# pmm.net
KiCad netlist of a schematic drawn in EAGLE
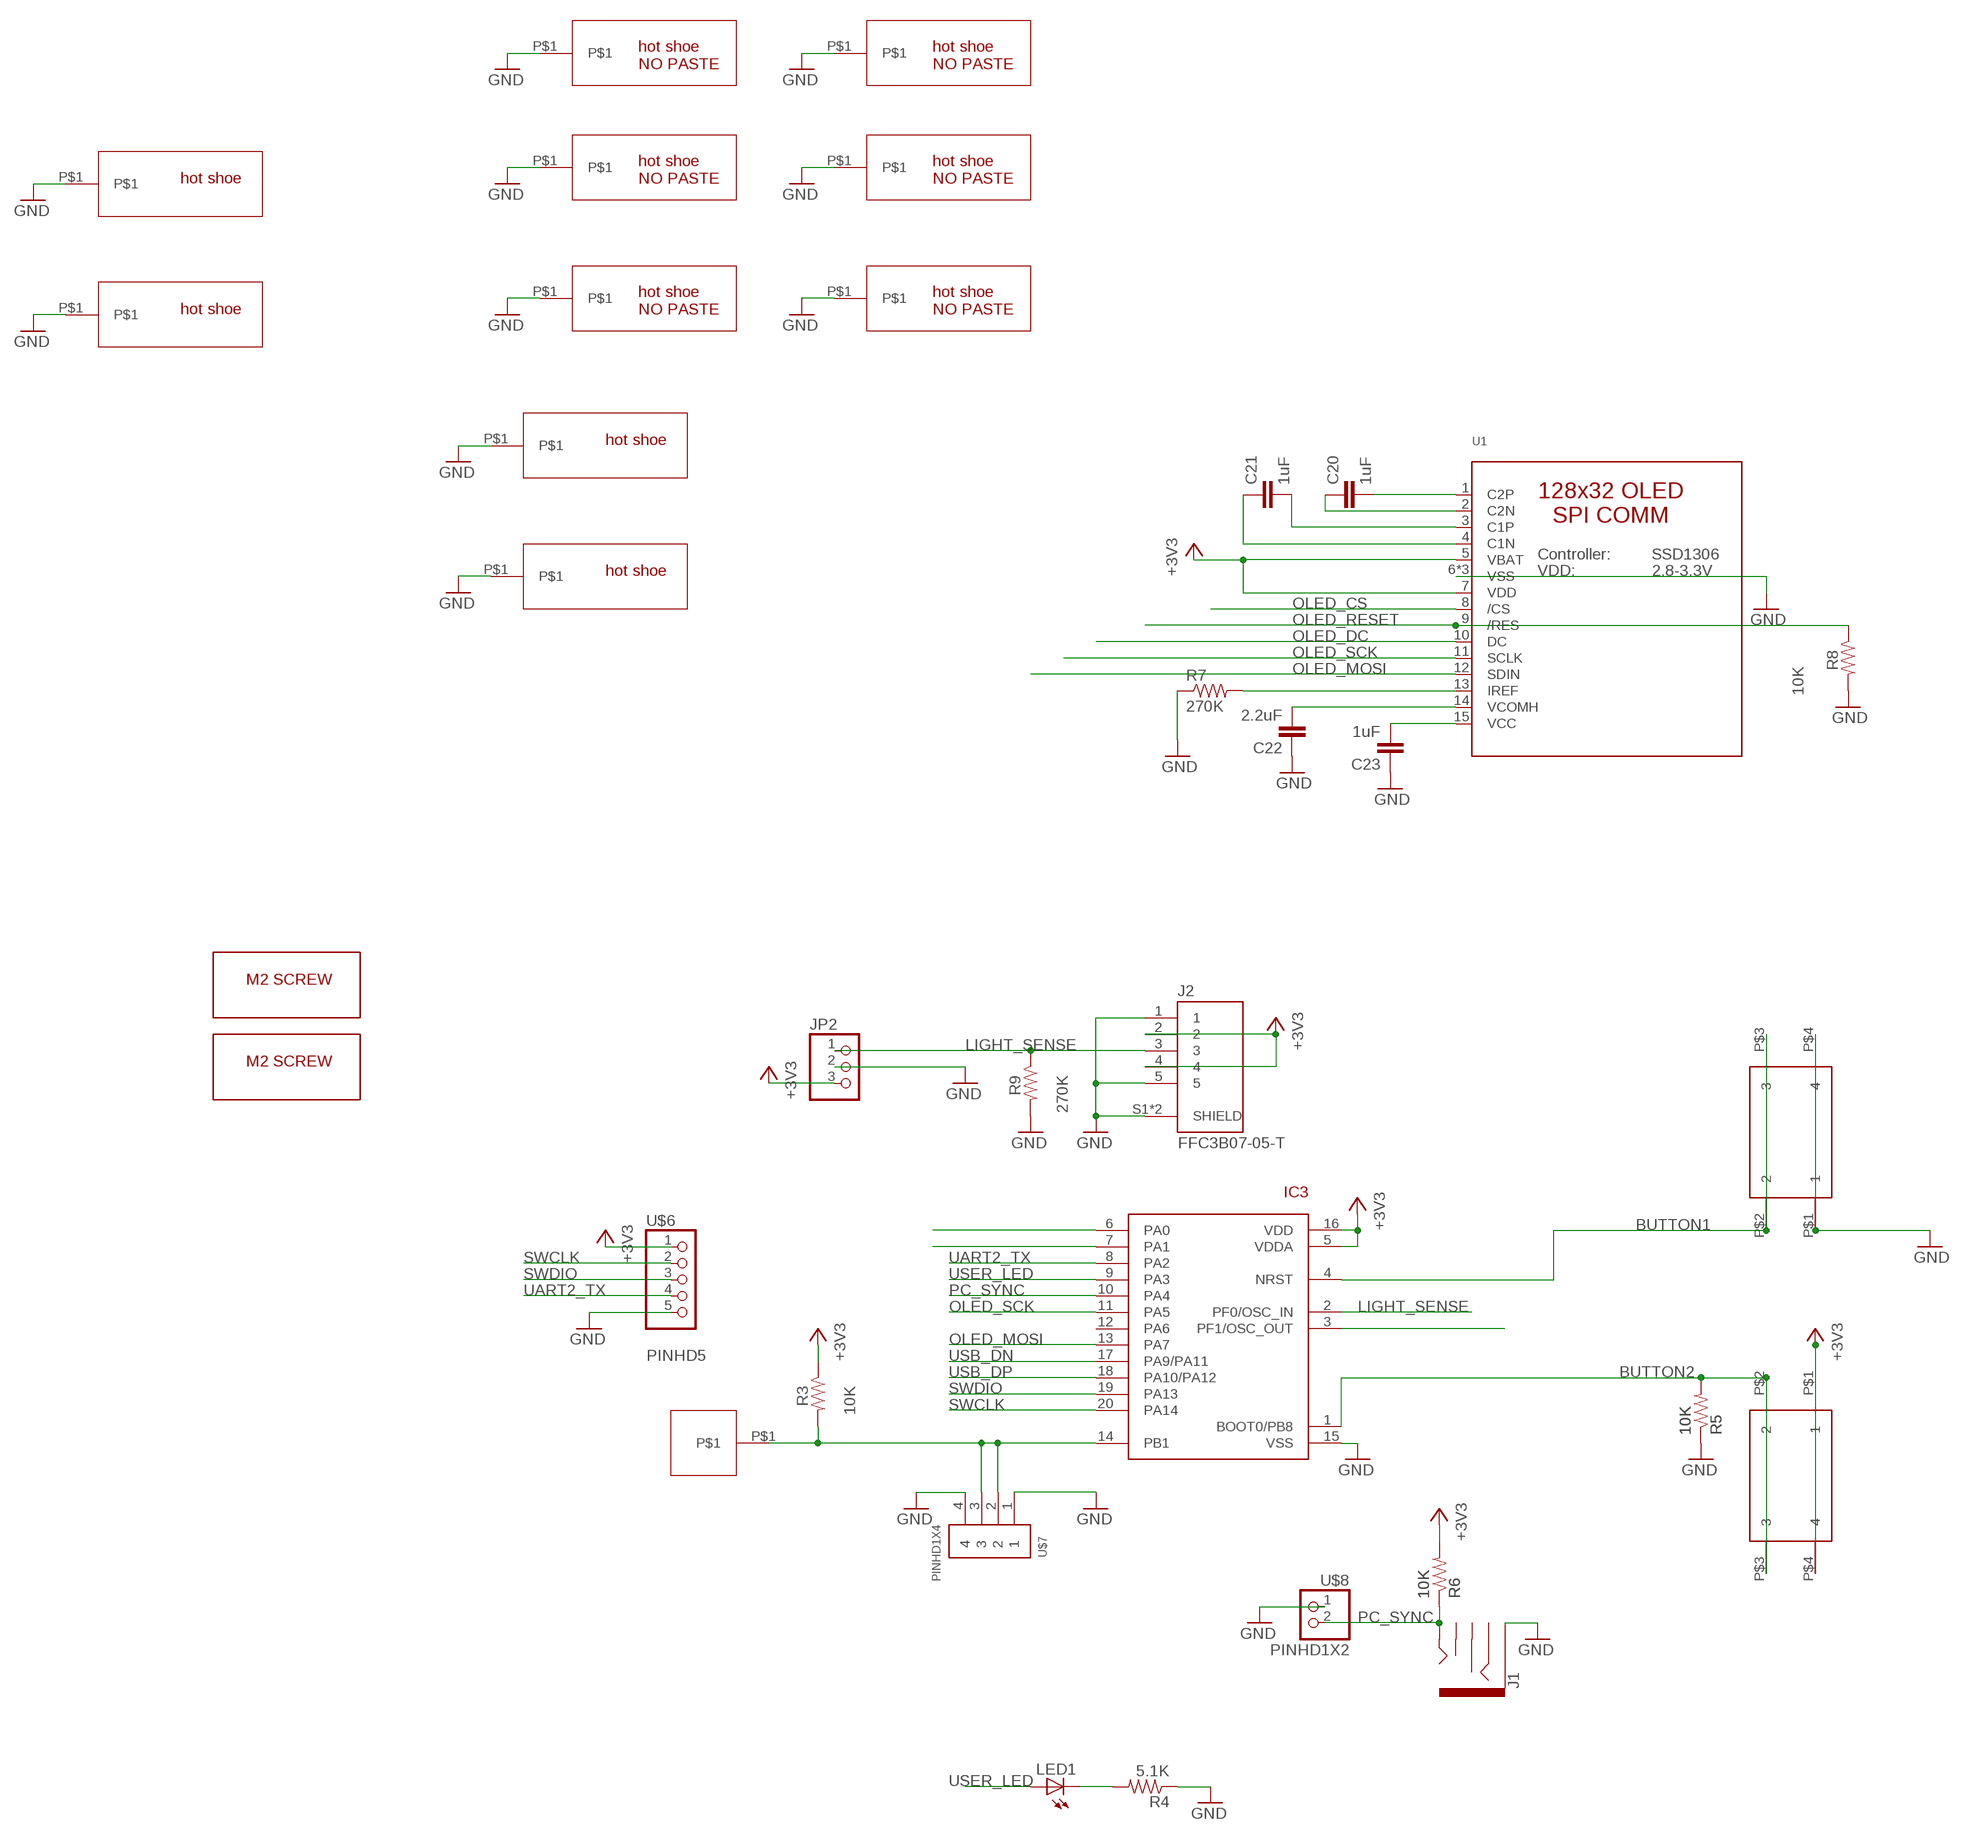
[diagram p0: schematic, sheet 1, part 1 of 2]
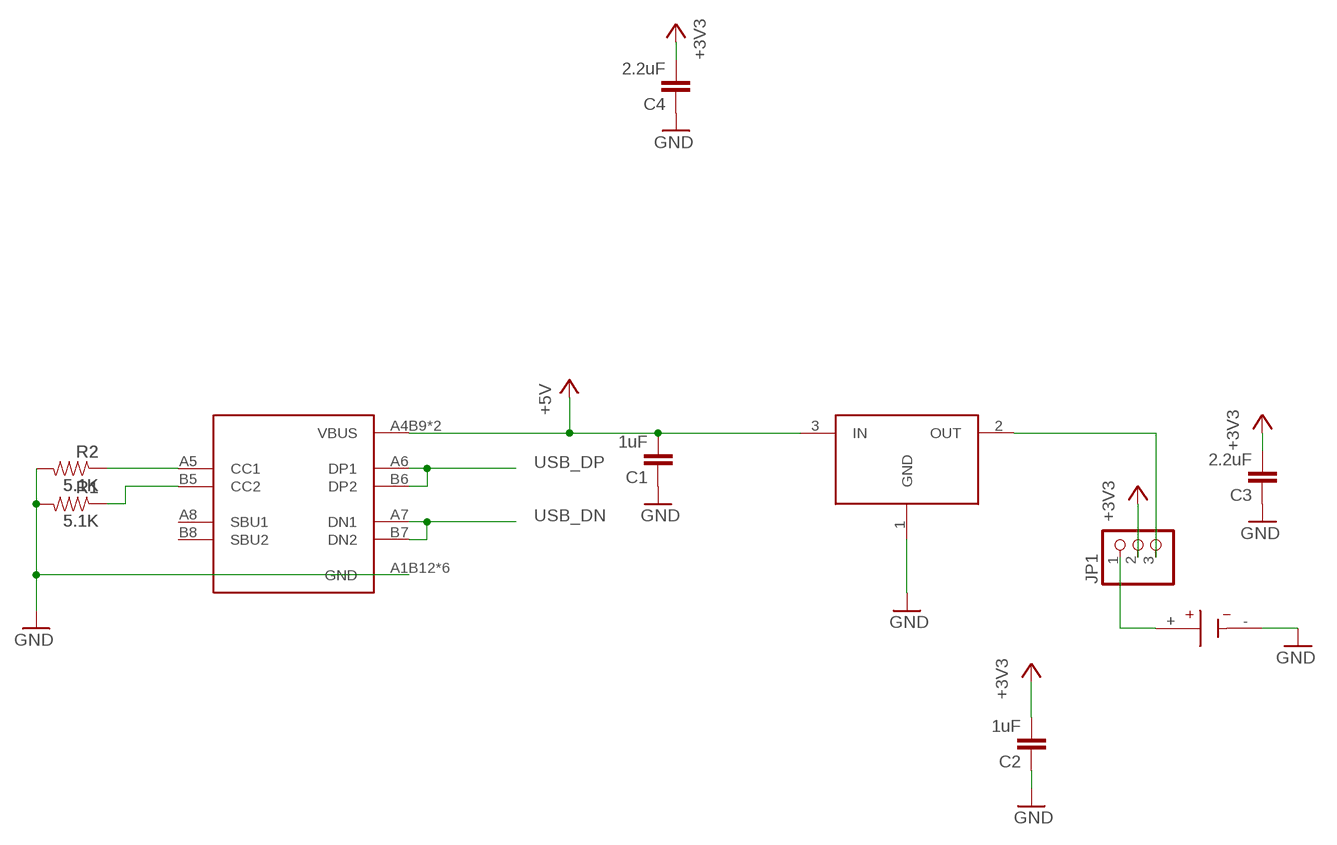
[diagram p1: schematic, sheet 1, part 2 of 2]

(export (version "E")
  (design (tool "Eeschema 10.0.6"))
  (components
    (comp (ref "BT1")
      (value "BU2032SM-G")
      (footprint "eagle-import:BAT_BU2032SM-G")
      (fields (field (name "MF") "MPD"))
      (libsource (lib "eagle-import") (part "BU2032SM-G"))
    )
    (comp (ref "C1")
      (value "1uF")
      (footprint "eagle-import:0805")
      (libsource (lib "eagle-import") (part "CAP0805"))
    )
    (comp (ref "C2")
      (value "1uF")
      (footprint "eagle-import:0805")
      (libsource (lib "eagle-import") (part "CAP0805"))
    )
    (comp (ref "C3")
      (value "2.2uF")
      (footprint "eagle-import:0805")
      (libsource (lib "eagle-import") (part "CAP0805"))
    )
    (comp (ref "C4")
      (value "2.2uF")
      (footprint "eagle-import:0805")
      (libsource (lib "eagle-import") (part "CAP0805"))
    )
    (comp (ref "C20")
      (value "1uF")
      (footprint "eagle-import:0805")
      (libsource (lib "eagle-import") (part "CAP0805"))
    )
    (comp (ref "C21")
      (value "1uF")
      (footprint "eagle-import:0805")
      (libsource (lib "eagle-import") (part "CAP0805"))
    )
    (comp (ref "C22")
      (value "2.2uF")
      (footprint "eagle-import:0805")
      (libsource (lib "eagle-import") (part "CAP0805"))
    )
    (comp (ref "C23")
      (value "1uF")
      (footprint "eagle-import:0805")
      (libsource (lib "eagle-import") (part "CAP0805"))
    )
    (comp (ref "IC3")
      (value "STM32F042F4")
      (footprint "eagle-import:TSSOP20")
      (libsource (lib "eagle-import") (part "STM32F042F4"))
    )
    (comp (ref "J1")
      (value "AUDIO_JACK_3.5MM_PTH")
      (footprint "eagle-import:AUDIO-JACK")
      (libsource (lib "eagle-import") (part "AUDIO_JACK_3.5MM_PTH"))
    )
    (comp (ref "J2")
      (value "FFC3B07-05-T")
      (footprint "eagle-import:GCT_FFC3B07-05-T")
      (fields (field (name "MF") "Global Connector Technology"))
      (libsource (lib "eagle-import") (part "FFC3B07-05-T"))
    )
    (comp (ref "JP1")
      (value "PINHD-1X3CB")
      (footprint "eagle-import:1X03-CLEANBIG")
      (libsource (lib "eagle-import") (part "PINHD-1X3CB"))
    )
    (comp (ref "JP2")
      (value "PINHD-1X3CB")
      (footprint "eagle-import:1X03-CLEANBIG")
      (libsource (lib "eagle-import") (part "PINHD-1X3CB"))
    )
    (comp (ref "LED1")
      (value "LEDCHIP-LED0805")
      (footprint "eagle-import:CHIP-LED0805")
      (libsource (lib "eagle-import") (part "LEDCHIP-LED0805"))
    )
    (comp (ref "R1")
      (value "5.1K")
      (footprint "eagle-import:0805")
      (libsource (lib "eagle-import") (part "joyAnalog_RESISTOR0805-RES"))
    )
    (comp (ref "R2")
      (value "5.1K")
      (footprint "eagle-import:0805")
      (libsource (lib "eagle-import") (part "joyAnalog_RESISTOR0805-RES"))
    )
    (comp (ref "R3")
      (value "10K")
      (footprint "eagle-import:0805")
      (libsource (lib "eagle-import") (part "joyAnalog_RESISTOR0805-RES"))
    )
    (comp (ref "R4")
      (value "5.1K")
      (footprint "eagle-import:0805")
      (libsource (lib "eagle-import") (part "RESISTOR0805-RES"))
    )
    (comp (ref "R5")
      (value "10K")
      (footprint "eagle-import:0805")
      (libsource (lib "eagle-import") (part "joyAnalog_RESISTOR0805-RES"))
    )
    (comp (ref "R6")
      (value "10K")
      (footprint "eagle-import:0805")
      (libsource (lib "eagle-import") (part "joyAnalog_RESISTOR0805-RES"))
    )
    (comp (ref "R7")
      (value "270K")
      (footprint "eagle-import:0805")
      (libsource (lib "eagle-import") (part "RESISTOR0805-RES"))
    )
    (comp (ref "R8")
      (value "10K")
      (footprint "eagle-import:0805")
      (libsource (lib "eagle-import") (part "joyAnalog_RESISTOR0805-RES"))
    )
    (comp (ref "R9")
      (value "270K")
      (footprint "eagle-import:0805")
      (libsource (lib "eagle-import") (part "joyAnalog_RESISTOR0805-RES"))
    )
    (comp (ref "SW3")
      (value "324_SW")
      (footprint "eagle-import:342_SWICH_FOOT")
      (libsource (lib "eagle-import") (part "324_SW"))
    )
    (comp (ref "SW4")
      (value "324_SW")
      (footprint "eagle-import:342_SWICH_FOOT")
      (libsource (lib "eagle-import") (part "324_SW"))
    )
    (comp (ref "U$1")
      (value "M2_SCREW_DEV")
      (footprint "eagle-import:M2_SCREW_FOOT")
      (libsource (lib "eagle-import") (part "M2_SCREW_DEV"))
    )
    (comp (ref "U$2")
      (value "SPRING_CONTACT")
      (footprint "eagle-import:SPRING_CONTACT")
      (libsource (lib "eagle-import") (part "SPRING_CONTACT"))
    )
    (comp (ref "U$3")
      (value "HOTSHOE")
      (footprint "eagle-import:HOTSHOE_RAIL")
      (libsource (lib "eagle-import") (part "HOTSHOE"))
    )
    (comp (ref "U$4")
      (value "HOTSHOE")
      (footprint "eagle-import:HOTSHOE_RAIL")
      (libsource (lib "eagle-import") (part "HOTSHOE"))
    )
    (comp (ref "U$5")
      (value "HOTSHOE_NOPASTE")
      (footprint "eagle-import:HOTSHOE_RAIL_NOPASTE")
      (libsource (lib "eagle-import") (part "HOTSHOE_NOPASTE"))
    )
    (comp (ref "U$6")
      (value "PINHD5")
      (footprint "eagle-import:1X05")
      (libsource (lib "eagle-import") (part "PINHD5"))
    )
    (comp (ref "U$7")
      (value "PINHD1X4")
      (footprint "eagle-import:1X04-CLEANBIG")
      (libsource (lib "eagle-import") (part "PINHD1X4"))
    )
    (comp (ref "U$8")
      (value "PINHD1X2")
      (footprint "eagle-import:1X02")
      (libsource (lib "eagle-import") (part "PINHD1X2"))
    )
    (comp (ref "U$9")
      (value "HOTSHOE_NOPASTE")
      (footprint "eagle-import:HOTSHOE_RAIL_NOPASTE")
      (libsource (lib "eagle-import") (part "HOTSHOE_NOPASTE"))
    )
    (comp (ref "U$10")
      (value "HOTSHOE_NOPASTE")
      (footprint "eagle-import:HOTSHOE_RAIL_NOPASTE")
      (libsource (lib "eagle-import") (part "HOTSHOE_NOPASTE"))
    )
    (comp (ref "U$11")
      (value "HOTSHOE_NOPASTE")
      (footprint "eagle-import:HOTSHOE_RAIL_NOPASTE")
      (libsource (lib "eagle-import") (part "HOTSHOE_NOPASTE"))
    )
    (comp (ref "U$12")
      (value "M2_SCREW_DEV")
      (footprint "eagle-import:M2_SCREW_FOOT")
      (libsource (lib "eagle-import") (part "M2_SCREW_DEV"))
    )
    (comp (ref "U$13")
      (value "HOTSHOE_NOPASTE")
      (footprint "eagle-import:HOTSHOE_RAIL_NOPASTE")
      (libsource (lib "eagle-import") (part "HOTSHOE_NOPASTE"))
    )
    (comp (ref "U$14")
      (value "HOTSHOE")
      (footprint "eagle-import:HOTSHOE_RAIL")
      (libsource (lib "eagle-import") (part "HOTSHOE"))
    )
    (comp (ref "U$15")
      (value "HOTSHOE_NOPASTE")
      (footprint "eagle-import:HOTSHOE_RAIL_NOPASTE")
      (libsource (lib "eagle-import") (part "HOTSHOE_NOPASTE"))
    )
    (comp (ref "U$16")
      (value "HOTSHOE")
      (footprint "eagle-import:HOTSHOE_RAIL")
      (libsource (lib "eagle-import") (part "HOTSHOE"))
    )
    (comp (ref "U1")
      (value "LUL_DISP_OLED_UG-2864HSWEG01")
      (footprint "eagle-import:LUL_UG-2864HSWEG01_1.3_WRAPAROUND")
      (libsource (lib "eagle-import") (part "LUL_DISP_OLED_UG-2864HSWEG01"))
    )
    (comp (ref "U2")
      (value "USBC_16P")
      (footprint "eagle-import:USBC_16P_FOOT")
      (libsource (lib "eagle-import") (part "USBC_16P"))
    )
    (comp (ref "U4")
      (value "XC6206_DEV")
      (footprint "eagle-import:SOT23R_INFINEON")
      (libsource (lib "eagle-import") (part "XC6206_DEV"))
    )
  )
  (nets
    (net (code "1") (name "+3V3") (class "Default")
      (node (ref "C2") (pin "2") (pinfunction "2_2") (pintype "passive"))
      (node (ref "C3") (pin "2") (pinfunction "2_2") (pintype "passive"))
      (node (ref "C4") (pin "2") (pinfunction "2_2") (pintype "passive"))
      (node (ref "IC3") (pin "16") (pinfunction "VDD_16") (pintype "bidirectional"))
      (node (ref "IC3") (pin "5") (pinfunction "VDDA_5") (pintype "bidirectional"))
      (node (ref "J2") (pin "2") (pinfunction "2_2") (pintype "passive"))
      (node (ref "J2") (pin "4") (pinfunction "4_4") (pintype "passive"))
      (node (ref "JP1") (pin "2") (pinfunction "2_2") (pintype "passive"))
      (node (ref "JP2") (pin "3") (pinfunction "3_3") (pintype "passive"))
      (node (ref "R3") (pin "1") (pinfunction "1_1") (pintype "passive"))
      (node (ref "R6") (pin "2") (pinfunction "2_2") (pintype "passive"))
      (node (ref "SW4") (pin "P$1") (pinfunction "1_P$1") (pintype "bidirectional"))
      (node (ref "SW4") (pin "P$4") (pinfunction "4_P$4") (pintype "bidirectional"))
      (node (ref "U$6") (pin "1") (pinfunction "1_1") (pintype "passive"))
      (node (ref "U1") (pin "5") (pinfunction "VBAT_5") (pintype "input"))
      (node (ref "U1") (pin "7") (pinfunction "VDD_7") (pintype "power_in"))
    )
    (net (code "2") (name "+5V") (class "Default")
      (node (ref "C1") (pin "2") (pinfunction "2_2") (pintype "passive"))
      (node (ref "U2") (pin "A4B9") (pinfunction "VBUS_A4B9") (pintype "bidirectional"))
      (node (ref "U2") (pin "B4A9") (pinfunction "VBUS_B4A9") (pintype "bidirectional"))
      (node (ref "U4") (pin "3") (pinfunction "IN_3") (pintype "bidirectional"))
    )
    (net (code "3") (name "/BUTTON1") (class "Default")
      (node (ref "IC3") (pin "4") (pinfunction "NRST_4") (pintype "bidirectional"))
      (node (ref "SW3") (pin "P$2") (pinfunction "2_P$2") (pintype "bidirectional"))
      (node (ref "SW3") (pin "P$3") (pinfunction "3_P$3") (pintype "bidirectional"))
    )
    (net (code "4") (name "/BUTTON2") (class "Default")
      (node (ref "IC3") (pin "1") (pinfunction "BOOT0/PB8_1") (pintype "bidirectional"))
      (node (ref "R5") (pin "2") (pinfunction "2_2") (pintype "passive"))
      (node (ref "SW4") (pin "P$2") (pinfunction "2_P$2") (pintype "bidirectional"))
      (node (ref "SW4") (pin "P$3") (pinfunction "3_P$3") (pintype "bidirectional"))
    )
    (net (code "5") (name "/LIGHT_SENSE") (class "Default")
      (node (ref "IC3") (pin "2") (pinfunction "PF0/OSC_IN_2") (pintype "bidirectional"))
      (node (ref "J2") (pin "3") (pinfunction "3_3") (pintype "passive"))
      (node (ref "JP2") (pin "1") (pinfunction "1_1") (pintype "passive"))
      (node (ref "R9") (pin "1") (pinfunction "1_1") (pintype "passive"))
    )
    (net (code "6") (name "/OLED_CS") (class "Default")
      (node (ref "IC3") (pin "3") (pinfunction "PF1/OSC_OUT_3") (pintype "bidirectional"))
      (node (ref "U1") (pin "8") (pinfunction "/CS_8") (pintype "input"))
    )
    (net (code "7") (name "/OLED_DC") (class "Default")
      (node (ref "IC3") (pin "7") (pinfunction "PA1_7") (pintype "bidirectional"))
      (node (ref "U1") (pin "10") (pinfunction "DC_10") (pintype "input"))
    )
    (net (code "8") (name "/OLED_MOSI") (class "Default")
      (node (ref "IC3") (pin "13") (pinfunction "PA7_13") (pintype "bidirectional"))
      (node (ref "U1") (pin "12") (pinfunction "SDIN_12") (pintype "bidirectional"))
    )
    (net (code "9") (name "/OLED_RESET") (class "Default")
      (node (ref "IC3") (pin "6") (pinfunction "PA0_6") (pintype "bidirectional"))
      (node (ref "R8") (pin "1") (pinfunction "1_1") (pintype "passive"))
      (node (ref "U1") (pin "9") (pinfunction "/RES_9") (pintype "input"))
    )
    (net (code "10") (name "/OLED_SCK") (class "Default")
      (node (ref "IC3") (pin "11") (pinfunction "PA5_11") (pintype "bidirectional"))
      (node (ref "U1") (pin "11") (pinfunction "SCLK_11") (pintype "bidirectional"))
    )
    (net (code "11") (name "/PC_SYNC") (class "Default")
      (node (ref "IC3") (pin "10") (pinfunction "PA4_10") (pintype "bidirectional"))
      (node (ref "J1") (pin "TIP") (pinfunction "TIP_TIP") (pintype "bidirectional"))
      (node (ref "R6") (pin "1") (pinfunction "1_1") (pintype "passive"))
      (node (ref "U$8") (pin "2") (pinfunction "2_2") (pintype "passive"))
    )
    (net (code "12") (name "/SWCLK") (class "Default")
      (node (ref "IC3") (pin "20") (pinfunction "PA14_20") (pintype "bidirectional"))
      (node (ref "U$6") (pin "2") (pinfunction "2_2") (pintype "passive"))
    )
    (net (code "13") (name "/SWDIO") (class "Default")
      (node (ref "IC3") (pin "19") (pinfunction "PA13_19") (pintype "bidirectional"))
      (node (ref "U$6") (pin "3") (pinfunction "3_3") (pintype "passive"))
    )
    (net (code "14") (name "/UART2_TX") (class "Default")
      (node (ref "IC3") (pin "8") (pinfunction "PA2_8") (pintype "bidirectional"))
      (node (ref "U$6") (pin "4") (pinfunction "4_4") (pintype "passive"))
    )
    (net (code "15") (name "/USB_DN") (class "Default")
      (node (ref "IC3") (pin "17") (pinfunction "PA9/PA11_17") (pintype "bidirectional"))
      (node (ref "U2") (pin "A7") (pinfunction "DN1_A7") (pintype "bidirectional"))
      (node (ref "U2") (pin "B7") (pinfunction "DN2_B7") (pintype "bidirectional"))
    )
    (net (code "16") (name "/USB_DP") (class "Default")
      (node (ref "IC3") (pin "18") (pinfunction "PA10/PA12_18") (pintype "bidirectional"))
      (node (ref "U2") (pin "A6") (pinfunction "DP1_A6") (pintype "bidirectional"))
      (node (ref "U2") (pin "B6") (pinfunction "DP2_B6") (pintype "bidirectional"))
    )
    (net (code "17") (name "/USER_LED") (class "Default")
      (node (ref "IC3") (pin "9") (pinfunction "PA3_9") (pintype "bidirectional"))
      (node (ref "LED1") (pin "A") (pinfunction "A_A") (pintype "passive"))
    )
    (net (code "18") (name "GND") (class "Default")
      (node (ref "BT1") (pin "-") (pinfunction "-_-") (pintype "passive"))
      (node (ref "C1") (pin "1") (pinfunction "1_1") (pintype "passive"))
      (node (ref "C2") (pin "1") (pinfunction "1_1") (pintype "passive"))
      (node (ref "C22") (pin "1") (pinfunction "1_1") (pintype "passive"))
      (node (ref "C23") (pin "1") (pinfunction "1_1") (pintype "passive"))
      (node (ref "C3") (pin "1") (pinfunction "1_1") (pintype "passive"))
      (node (ref "C4") (pin "1") (pinfunction "1_1") (pintype "passive"))
      (node (ref "IC3") (pin "15") (pinfunction "VSS_15") (pintype "bidirectional"))
      (node (ref "J1") (pin "SLEEVE") (pinfunction "SLEEVE_SLEEVE") (pintype "bidirectional"))
      (node (ref "J2") (pin "1") (pinfunction "1_1") (pintype "passive"))
      (node (ref "J2") (pin "5") (pinfunction "5_5") (pintype "passive"))
      (node (ref "J2") (pin "S1") (pinfunction "SHIELD_S1") (pintype "passive"))
      (node (ref "J2") (pin "S2") (pinfunction "SHIELD_S2") (pintype "passive"))
      (node (ref "JP2") (pin "2") (pinfunction "2_2") (pintype "passive"))
      (node (ref "R1") (pin "2") (pinfunction "2_2") (pintype "passive"))
      (node (ref "R2") (pin "2") (pinfunction "2_2") (pintype "passive"))
      (node (ref "R4") (pin "1") (pinfunction "1_1") (pintype "passive"))
      (node (ref "R5") (pin "1") (pinfunction "1_1") (pintype "passive"))
      (node (ref "R7") (pin "1") (pinfunction "1_1") (pintype "passive"))
      (node (ref "R8") (pin "2") (pinfunction "2_2") (pintype "passive"))
      (node (ref "R9") (pin "2") (pinfunction "2_2") (pintype "passive"))
      (node (ref "SW3") (pin "P$1") (pinfunction "1_P$1") (pintype "bidirectional"))
      (node (ref "SW3") (pin "P$4") (pinfunction "4_P$4") (pintype "bidirectional"))
      (node (ref "U$10") (pin "P$1") (pinfunction "P$1_P$1") (pintype "bidirectional"))
      (node (ref "U$11") (pin "P$1") (pinfunction "P$1_P$1") (pintype "bidirectional"))
      (node (ref "U$13") (pin "P$1") (pinfunction "P$1_P$1") (pintype "bidirectional"))
      (node (ref "U$14") (pin "P$1") (pinfunction "P$1_P$1") (pintype "bidirectional"))
      (node (ref "U$15") (pin "P$1") (pinfunction "P$1_P$1") (pintype "bidirectional"))
      (node (ref "U$16") (pin "P$1") (pinfunction "P$1_P$1") (pintype "bidirectional"))
      (node (ref "U$3") (pin "P$1") (pinfunction "P$1_P$1") (pintype "bidirectional"))
      (node (ref "U$4") (pin "P$1") (pinfunction "P$1_P$1") (pintype "bidirectional"))
      (node (ref "U$5") (pin "P$1") (pinfunction "P$1_P$1") (pintype "bidirectional"))
      (node (ref "U$6") (pin "5") (pinfunction "5_5") (pintype "passive"))
      (node (ref "U$7") (pin "1") (pinfunction "1_1") (pintype "bidirectional"))
      (node (ref "U$7") (pin "4") (pinfunction "4_4") (pintype "bidirectional"))
      (node (ref "U$8") (pin "1") (pinfunction "1_1") (pintype "passive"))
      (node (ref "U$9") (pin "P$1") (pinfunction "P$1_P$1") (pintype "bidirectional"))
      (node (ref "U1") (pin "16") (pinfunction "VSS_16") (pintype "power_in"))
      (node (ref "U1") (pin "17") (pinfunction "VSS_17") (pintype "power_in"))
      (node (ref "U1") (pin "6") (pinfunction "VSS_6") (pintype "power_in"))
      (node (ref "U2") (pin "A1B12") (pinfunction "GND_A1B12") (pintype "bidirectional"))
      (node (ref "U2") (pin "B11A12") (pinfunction "GND_B11A12") (pintype "bidirectional"))
      (node (ref "U2") (pin "P$13") (pinfunction "GND_P$13") (pintype "bidirectional"))
      (node (ref "U2") (pin "P$14") (pinfunction "GND_P$14") (pintype "bidirectional"))
      (node (ref "U2") (pin "P$15") (pinfunction "GND_P$15") (pintype "bidirectional"))
      (node (ref "U2") (pin "P$16") (pinfunction "GND_P$16") (pintype "bidirectional"))
      (node (ref "U4") (pin "1") (pinfunction "GND_1") (pintype "bidirectional"))
    )
    (net (code "19") (name "Net-(BT1-Pad+)") (class "Default")
      (node (ref "BT1") (pin "+") (pinfunction "+_+") (pintype "passive"))
      (node (ref "JP1") (pin "1") (pinfunction "1_1") (pintype "passive"))
    )
    (net (code "20") (name "Net-(IC3-PB1)") (class "Default")
      (node (ref "IC3") (pin "14") (pinfunction "PB1_14") (pintype "bidirectional"))
      (node (ref "R3") (pin "2") (pinfunction "2_2") (pintype "passive"))
      (node (ref "U$2") (pin "P$1") (pinfunction "P$1_P$1") (pintype "bidirectional"))
      (node (ref "U$7") (pin "2") (pinfunction "2_2") (pintype "bidirectional"))
      (node (ref "U$7") (pin "3") (pinfunction "3_3") (pintype "bidirectional"))
    )
    (net (code "21") (name "Net-(LED1-PadC)") (class "Default")
      (node (ref "LED1") (pin "C") (pinfunction "C_C") (pintype "passive"))
      (node (ref "R4") (pin "2") (pinfunction "2_2") (pintype "passive"))
    )
    (net (code "22") (name "Net-(U1-C1N)") (class "Default")
      (node (ref "C21") (pin "1") (pinfunction "1_1") (pintype "passive"))
      (node (ref "U1") (pin "4") (pinfunction "C1N_4") (pintype "input"))
    )
    (net (code "23") (name "Net-(U1-C1P)") (class "Default")
      (node (ref "C21") (pin "2") (pinfunction "2_2") (pintype "passive"))
      (node (ref "U1") (pin "3") (pinfunction "C1P_3") (pintype "input"))
    )
    (net (code "24") (name "Net-(U1-C2N)") (class "Default")
      (node (ref "C20") (pin "1") (pinfunction "1_1") (pintype "passive"))
      (node (ref "U1") (pin "2") (pinfunction "C2N_2") (pintype "input"))
    )
    (net (code "25") (name "Net-(U1-C2P)") (class "Default")
      (node (ref "C20") (pin "2") (pinfunction "2_2") (pintype "passive"))
      (node (ref "U1") (pin "1") (pinfunction "C2P_1") (pintype "input"))
    )
    (net (code "26") (name "Net-(U1-IREF)") (class "Default")
      (node (ref "R7") (pin "2") (pinfunction "2_2") (pintype "passive"))
      (node (ref "U1") (pin "13") (pinfunction "IREF_13") (pintype "input"))
    )
    (net (code "27") (name "Net-(U1-VCC)") (class "Default")
      (node (ref "C23") (pin "2") (pinfunction "2_2") (pintype "passive"))
      (node (ref "U1") (pin "15") (pinfunction "VCC_15") (pintype "power_in"))
    )
    (net (code "28") (name "Net-(U1-VCOMH)") (class "Default")
      (node (ref "C22") (pin "2") (pinfunction "2_2") (pintype "passive"))
      (node (ref "U1") (pin "14") (pinfunction "VCOMH_14") (pintype "output"))
    )
    (net (code "29") (name "Net-(U2-CC1)") (class "Default")
      (node (ref "R2") (pin "1") (pinfunction "1_1") (pintype "passive"))
      (node (ref "U2") (pin "A5") (pinfunction "CC1_A5") (pintype "bidirectional"))
    )
    (net (code "30") (name "Net-(U2-CC2)") (class "Default")
      (node (ref "R1") (pin "1") (pinfunction "1_1") (pintype "passive"))
      (node (ref "U2") (pin "B5") (pinfunction "CC2_B5") (pintype "bidirectional"))
    )
    (net (code "31") (name "Net-(U4-OUT)") (class "Default")
      (node (ref "JP1") (pin "3") (pinfunction "3_3") (pintype "passive"))
      (node (ref "U4") (pin "2") (pinfunction "OUT_2") (pintype "bidirectional"))
    )
    (net (code "32") (name "unconnected-(IC3-PA6-Pad12)") (class "Default")
      (node (ref "IC3") (pin "12") (pinfunction "PA6_12") (pintype "bidirectional"))
    )
    (net (code "33") (name "unconnected-(J1-PadRING)") (class "Default")
      (node (ref "J1") (pin "RING") (pinfunction "RING_RING") (pintype "bidirectional"))
    )
    (net (code "34") (name "unconnected-(J1-PadRSH)") (class "Default")
      (node (ref "J1") (pin "RSH") (pinfunction "RSH_RSH") (pintype "bidirectional"))
    )
    (net (code "35") (name "unconnected-(J1-PadTSH)") (class "Default")
      (node (ref "J1") (pin "TSH") (pinfunction "TSH_TSH") (pintype "bidirectional"))
    )
    (net (code "36") (name "unconnected-(U2-SBU1-PadA8)") (class "Default")
      (node (ref "U2") (pin "A8") (pinfunction "SBU1_A8") (pintype "bidirectional"))
    )
    (net (code "37") (name "unconnected-(U2-SBU2-PadB8)") (class "Default")
      (node (ref "U2") (pin "B8") (pinfunction "SBU2_B8") (pintype "bidirectional"))
    )
  )
)
